# pow_switch_sustainer.net
KiCad netlist of a schematic drawn in EAGLE
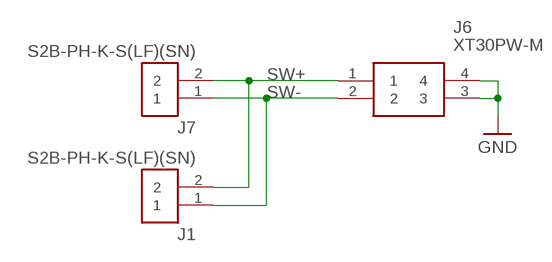
[diagram p0: schematic, sheet 1]

(export (version "E")
  (design (tool "Eeschema 10.0.6"))
  (components
    (comp (ref "J1")
      (value "S2B-PH-K-S(LF)(SN)")
      (footprint "eagle-import:S2B-PH-K-S(LF)(SN)")
      (fields
        (field (name "DIGI_KEY_PART_NUMBER") "455-1719-ND")
        (field (name "MANUFACTURER") "JST Sales America Inc.")
        (field (name "CREATED_BY") "PCBLayout.com")
      )
      (libsource (lib "eagle-import") (part "S2B-PH-K-S(LF)(SN)"))
    )
    (comp (ref "J6")
      (value "XT30PW-M")
      (footprint "eagle-import:XT30PWM")
      (libsource (lib "eagle-import") (part "XT30PW-M"))
    )
    (comp (ref "J7")
      (value "S2B-PH-K-S(LF)(SN)")
      (footprint "eagle-import:S2B-PH-K-S(LF)(SN)")
      (fields
        (field (name "DIGI_KEY_PART_NUMBER") "455-1719-ND")
        (field (name "MANUFACTURER") "JST Sales America Inc.")
        (field (name "CREATED_BY") "PCBLayout.com")
      )
      (libsource (lib "eagle-import") (part "S2B-PH-K-S(LF)(SN)"))
    )
  )
  (nets
    (net (code "1") (name "/SW+") (class "Default")
      (node (ref "J1") (pin "2") (pinfunction "2_2") (pintype "passive"))
      (node (ref "J6") (pin "1") (pinfunction "1_1") (pintype "bidirectional"))
      (node (ref "J7") (pin "2") (pinfunction "2_2") (pintype "passive"))
    )
    (net (code "2") (name "/SW-") (class "Default")
      (node (ref "J1") (pin "1") (pinfunction "1_1") (pintype "passive"))
      (node (ref "J6") (pin "2") (pinfunction "2_2") (pintype "bidirectional"))
      (node (ref "J7") (pin "1") (pinfunction "1_1") (pintype "passive"))
    )
    (net (code "3") (name "GND") (class "Default")
      (node (ref "J6") (pin "3") (pinfunction "3_3") (pintype "bidirectional"))
      (node (ref "J6") (pin "4") (pinfunction "4_4") (pintype "bidirectional"))
    )
  )
)
